# TK502_Frontpanel_LEDs.net
KiCad netlist of a schematic drawn in Altium Designer
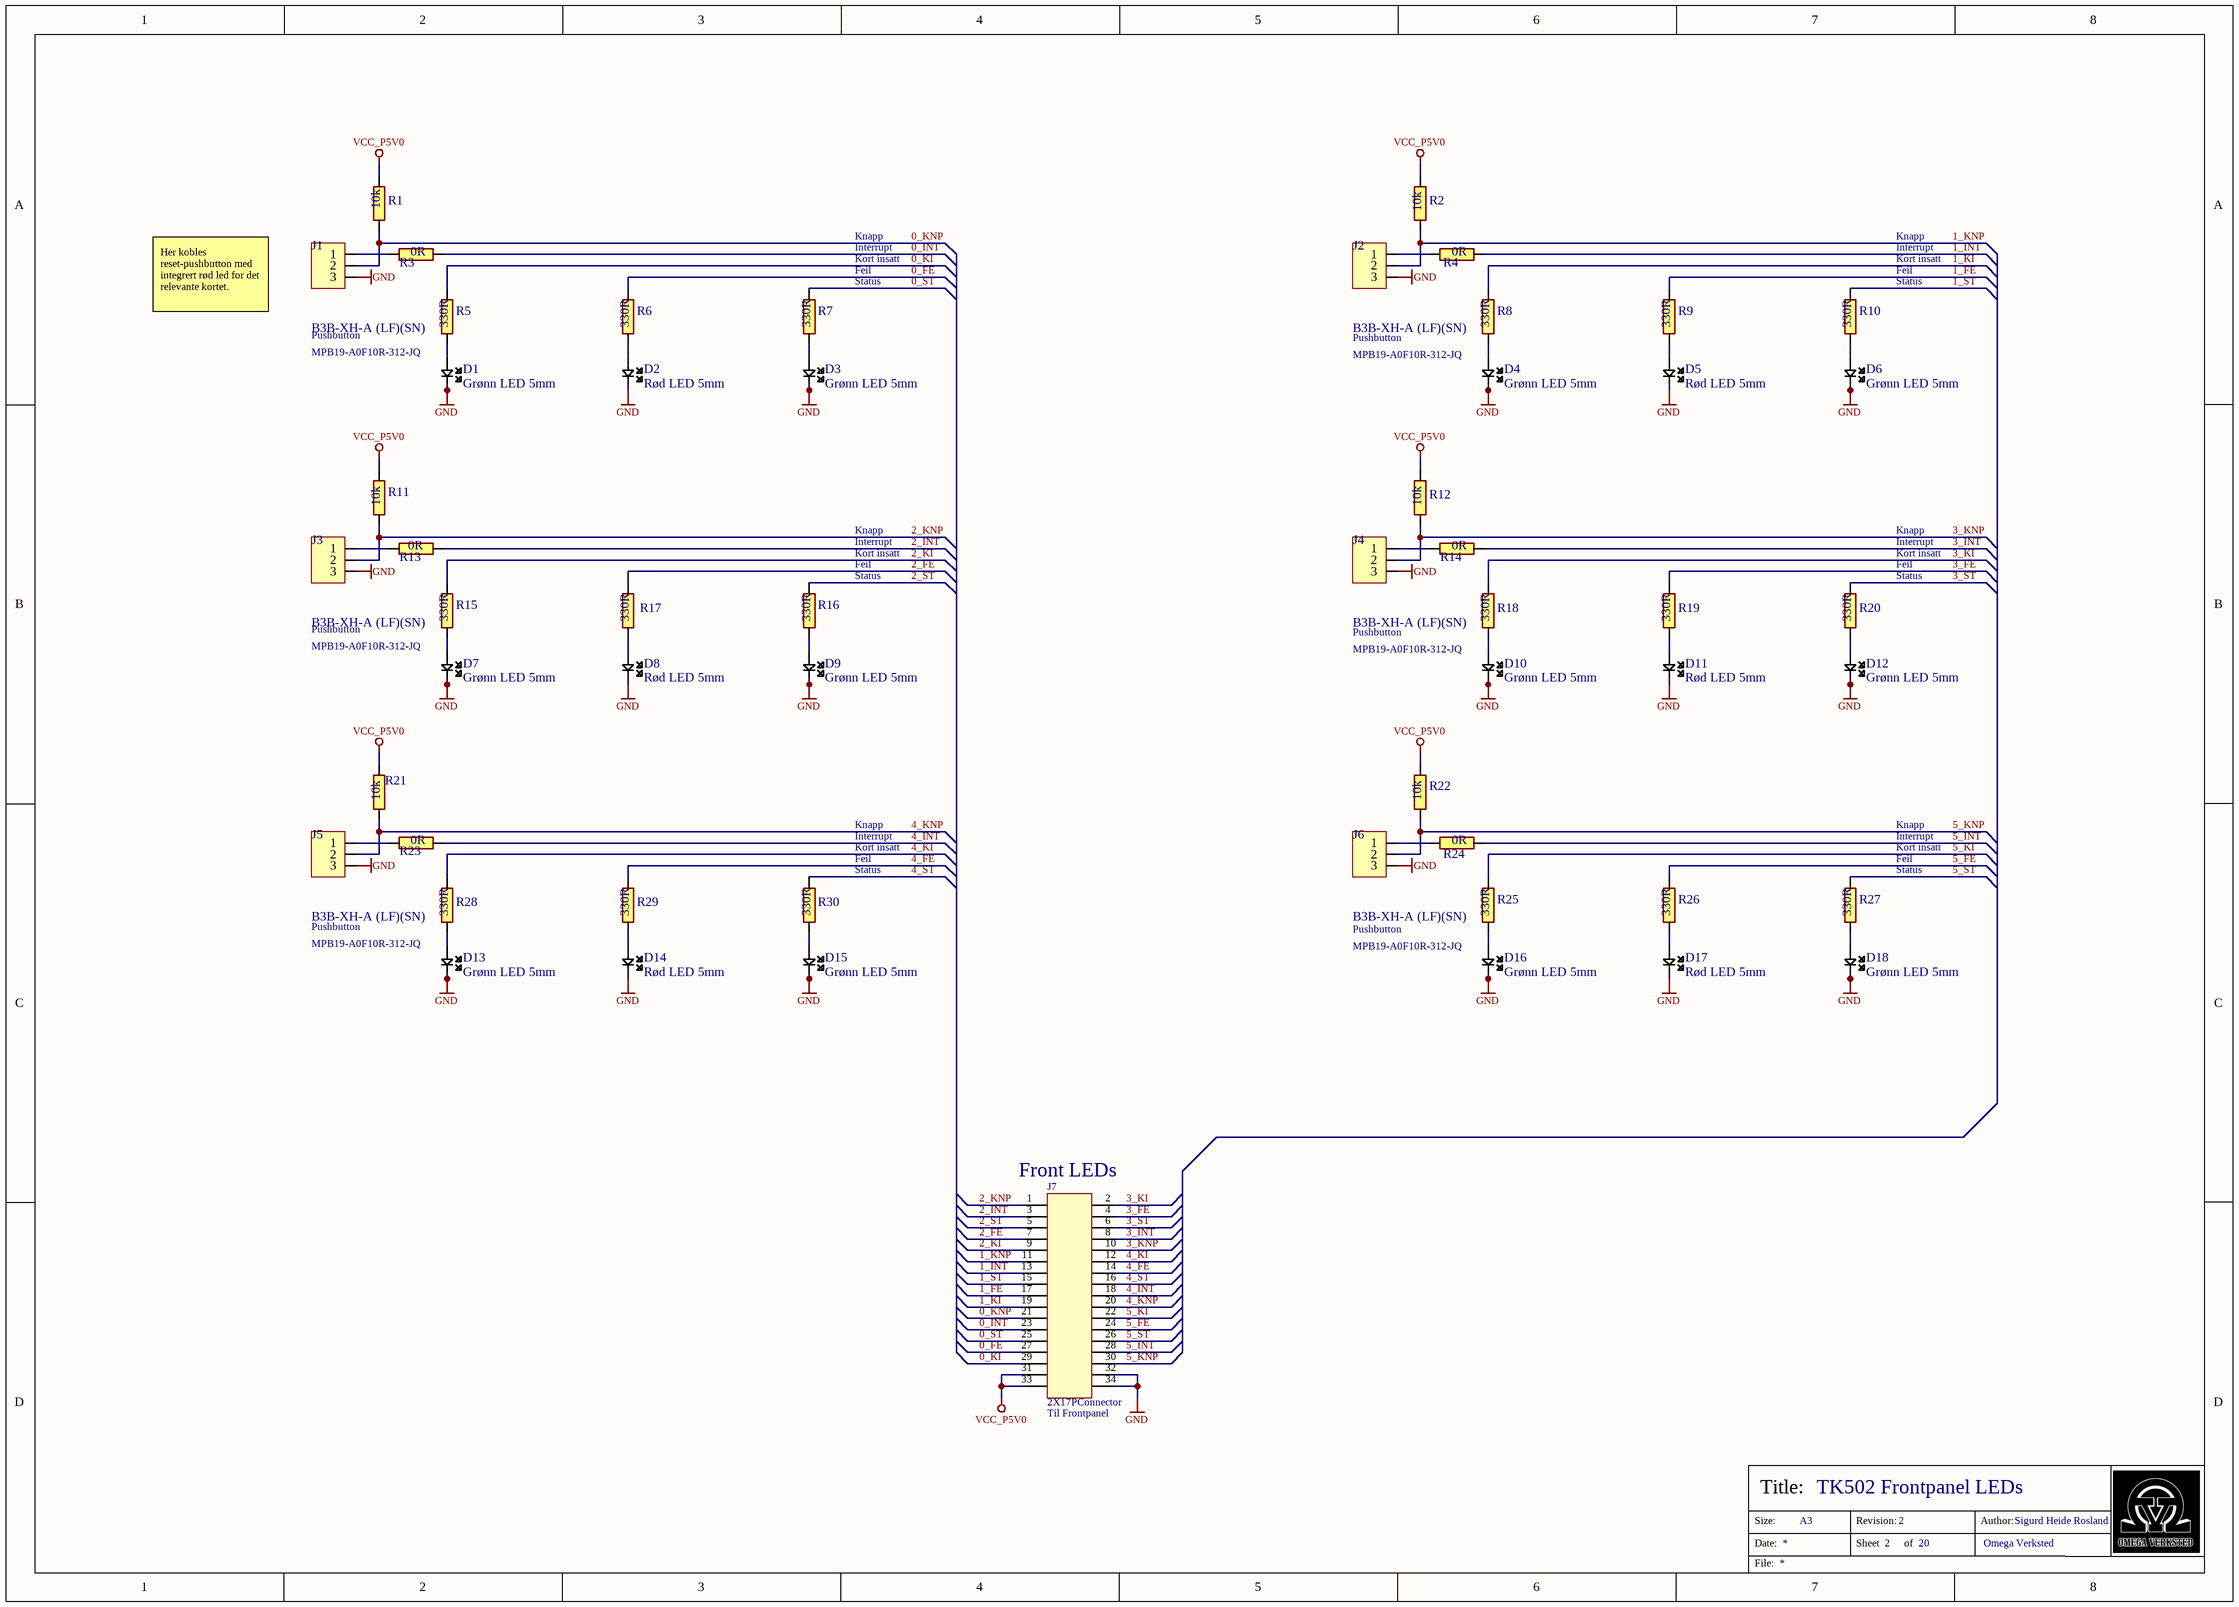
[diagram p0: TK502_Frontpanel_LEDs.SchDoc]

(export (version "E")
  (design (tool "Eeschema 10.0.6"))
  (components
    (comp (ref "D1")
      (value "Grønn LED 5mm")
      (footprint "LED254W7L870D500")
      (description "LED, Green, 5mm, 572 nm, 2.1 V, 20 mA, 150 mcd")
      (libsource (lib "OVLib_64") (part "LED"))
    )
    (comp (ref "D2")
      (value "Rød LED 5mm")
      (footprint "LED254W7L870D500")
      (description "LED, Red, 5mm, 643 nm, 1.8 V, 20 mA, 400 mcd")
      (libsource (lib "OVLib_64") (part "LED"))
    )
    (comp (ref "D3")
      (value "Grønn LED 5mm")
      (footprint "LED254W7L870D500")
      (description "LED, Green, 5mm, 572 nm, 2.1 V, 20 mA, 150 mcd")
      (libsource (lib "OVLib_64") (part "LED"))
    )
    (comp (ref "D4")
      (value "Grønn LED 5mm")
      (footprint "LED254W7L870D500")
      (description "LED, Green, 5mm, 572 nm, 2.1 V, 20 mA, 150 mcd")
      (libsource (lib "OVLib_64") (part "LED"))
    )
    (comp (ref "D5")
      (value "Rød LED 5mm")
      (footprint "LED254W7L870D500")
      (description "LED, Red, 5mm, 643 nm, 1.8 V, 20 mA, 400 mcd")
      (libsource (lib "OVLib_64") (part "LED"))
    )
    (comp (ref "D6")
      (value "Grønn LED 5mm")
      (footprint "LED254W7L870D500")
      (description "LED, Green, 5mm, 572 nm, 2.1 V, 20 mA, 150 mcd")
      (libsource (lib "OVLib_64") (part "LED"))
    )
    (comp (ref "D7")
      (value "Grønn LED 5mm")
      (footprint "LED254W7L870D500")
      (description "LED, Green, 5mm, 572 nm, 2.1 V, 20 mA, 150 mcd")
      (libsource (lib "OVLib_64") (part "LED"))
    )
    (comp (ref "D8")
      (value "Rød LED 5mm")
      (footprint "LED254W7L870D500")
      (description "LED, Red, 5mm, 643 nm, 1.8 V, 20 mA, 400 mcd")
      (libsource (lib "OVLib_64") (part "LED"))
    )
    (comp (ref "D9")
      (value "Grønn LED 5mm")
      (footprint "LED254W7L870D500")
      (description "LED, Green, 5mm, 572 nm, 2.1 V, 20 mA, 150 mcd")
      (libsource (lib "OVLib_64") (part "LED"))
    )
    (comp (ref "D10")
      (value "Grønn LED 5mm")
      (footprint "LED254W7L870D500")
      (description "LED, Green, 5mm, 572 nm, 2.1 V, 20 mA, 150 mcd")
      (libsource (lib "OVLib_64") (part "LED"))
    )
    (comp (ref "D11")
      (value "Rød LED 5mm")
      (footprint "LED254W7L870D500")
      (description "LED, Red, 5mm, 643 nm, 1.8 V, 20 mA, 400 mcd")
      (libsource (lib "OVLib_64") (part "LED"))
    )
    (comp (ref "D12")
      (value "Grønn LED 5mm")
      (footprint "LED254W7L870D500")
      (description "LED, Green, 5mm, 572 nm, 2.1 V, 20 mA, 150 mcd")
      (libsource (lib "OVLib_64") (part "LED"))
    )
    (comp (ref "D13")
      (value "Grønn LED 5mm")
      (footprint "LED254W7L870D500")
      (description "LED, Green, 5mm, 572 nm, 2.1 V, 20 mA, 150 mcd")
      (libsource (lib "OVLib_64") (part "LED"))
    )
    (comp (ref "D14")
      (value "Rød LED 5mm")
      (footprint "LED254W7L870D500")
      (description "LED, Red, 5mm, 643 nm, 1.8 V, 20 mA, 400 mcd")
      (libsource (lib "OVLib_64") (part "LED"))
    )
    (comp (ref "D15")
      (value "Grønn LED 5mm")
      (footprint "LED254W7L870D500")
      (description "LED, Green, 5mm, 572 nm, 2.1 V, 20 mA, 150 mcd")
      (libsource (lib "OVLib_64") (part "LED"))
    )
    (comp (ref "D16")
      (value "Grønn LED 5mm")
      (footprint "LED254W7L870D500")
      (description "LED, Green, 5mm, 572 nm, 2.1 V, 20 mA, 150 mcd")
      (libsource (lib "OVLib_64") (part "LED"))
    )
    (comp (ref "D17")
      (value "Rød LED 5mm")
      (footprint "LED254W7L870D500")
      (description "LED, Red, 5mm, 643 nm, 1.8 V, 20 mA, 400 mcd")
      (libsource (lib "OVLib_64") (part "LED"))
    )
    (comp (ref "D18")
      (value "Grønn LED 5mm")
      (footprint "LED254W7L870D500")
      (description "LED, Green, 5mm, 572 nm, 2.1 V, 20 mA, 150 mcd")
      (libsource (lib "OVLib_64") (part "LED"))
    )
    (comp (ref "J1")
      (value "B3B-XH-A (LF)(SN)")
      (footprint "JST_3P")
      (description "JST 3pin (pris pr. stk.)")
      (libsource (lib "OVLib_64") (part "3PConnector"))
    )
    (comp (ref "J2")
      (value "B3B-XH-A (LF)(SN)")
      (footprint "JST_3P")
      (description "JST 3pin (pris pr. stk.)")
      (libsource (lib "OVLib_64") (part "3PConnector"))
    )
    (comp (ref "J3")
      (value "B3B-XH-A (LF)(SN)")
      (footprint "JST_3P")
      (description "JST 3pin (pris pr. stk.)")
      (libsource (lib "OVLib_64") (part "3PConnector"))
    )
    (comp (ref "J4")
      (value "B3B-XH-A (LF)(SN)")
      (footprint "JST_3P")
      (description "JST 3pin (pris pr. stk.)")
      (libsource (lib "OVLib_64") (part "3PConnector"))
    )
    (comp (ref "J5")
      (value "B3B-XH-A (LF)(SN)")
      (footprint "JST_3P")
      (description "JST 3pin (pris pr. stk.)")
      (libsource (lib "OVLib_64") (part "3PConnector"))
    )
    (comp (ref "J6")
      (value "B3B-XH-A (LF)(SN)")
      (footprint "JST_3P")
      (description "JST 3pin (pris pr. stk.)")
      (libsource (lib "OVLib_64") (part "3PConnector"))
    )
    (comp (ref "J7")
      (value "2X17PConnector")
      (footprint "HDRV34W64P254_2X17_5070X900X900B")
      (description "Header")
      (libsource (lib "OVLib_64") (part "2X17PConnector"))
    )
    (comp (ref "R1")
      (value "10k")
      (footprint "RESC0603(1608)_N")
      (description "0.1W 1% Thick film resistor")
      (libsource (lib "OVLib_64") (part "Resistor2"))
    )
    (comp (ref "R2")
      (value "10k")
      (footprint "RESC0603(1608)_N")
      (description "0.1W 1% Thick film resistor")
      (libsource (lib "OVLib_64") (part "Resistor2"))
    )
    (comp (ref "R3")
      (value "0R")
      (footprint "RESC0603(1608)_N")
      (description "0.1W 1% Thick film resistor, Jumper")
      (libsource (lib "") (part "Resistor2_2"))
    )
    (comp (ref "R4")
      (value "0R")
      (footprint "RESC0603(1608)_N")
      (description "0.1W 1% Thick film resistor, Jumper")
      (libsource (lib "") (part "Resistor2_1"))
    )
    (comp (ref "R5")
      (value "330R")
      (footprint "RESC0603(1608)_N")
      (description "0.1W 1% Thick film resistor")
      (libsource (lib "OVLib_64") (part "Resistor2"))
    )
    (comp (ref "R6")
      (value "330R")
      (footprint "RESC0603(1608)_N")
      (description "0.1W 1% Thick film resistor")
      (libsource (lib "OVLib_64") (part "Resistor2"))
    )
    (comp (ref "R7")
      (value "330R")
      (footprint "RESC0603(1608)_N")
      (description "0.1W 1% Thick film resistor")
      (libsource (lib "OVLib_64") (part "Resistor2"))
    )
    (comp (ref "R8")
      (value "330R")
      (footprint "RESC0603(1608)_N")
      (description "0.1W 1% Thick film resistor")
      (libsource (lib "OVLib_64") (part "Resistor2"))
    )
    (comp (ref "R9")
      (value "330R")
      (footprint "RESC0603(1608)_N")
      (description "0.1W 1% Thick film resistor")
      (libsource (lib "OVLib_64") (part "Resistor2"))
    )
    (comp (ref "R10")
      (value "330R")
      (footprint "RESC0603(1608)_N")
      (description "0.1W 1% Thick film resistor")
      (libsource (lib "OVLib_64") (part "Resistor2"))
    )
    (comp (ref "R11")
      (value "10k")
      (footprint "RESC0603(1608)_N")
      (description "0.1W 1% Thick film resistor")
      (libsource (lib "OVLib_64") (part "Resistor2"))
    )
    (comp (ref "R12")
      (value "10k")
      (footprint "RESC0603(1608)_N")
      (description "0.1W 1% Thick film resistor")
      (libsource (lib "OVLib_64") (part "Resistor2"))
    )
    (comp (ref "R13")
      (value "0R")
      (footprint "RESC0603(1608)_N")
      (description "0.1W 1% Thick film resistor, Jumper")
      (libsource (lib "") (part "Resistor2_2"))
    )
    (comp (ref "R14")
      (value "0R")
      (footprint "RESC0603(1608)_N")
      (description "0.1W 1% Thick film resistor, Jumper")
      (libsource (lib "") (part "Resistor2_1"))
    )
    (comp (ref "R15")
      (value "330R")
      (footprint "RESC0603(1608)_N")
      (description "0.1W 1% Thick film resistor")
      (libsource (lib "OVLib_64") (part "Resistor2"))
    )
    (comp (ref "R16")
      (value "330R")
      (footprint "RESC0603(1608)_N")
      (description "0.1W 1% Thick film resistor")
      (libsource (lib "OVLib_64") (part "Resistor2"))
    )
    (comp (ref "R17")
      (value "330R")
      (footprint "RESC0603(1608)_N")
      (description "0.1W 1% Thick film resistor")
      (libsource (lib "OVLib_64") (part "Resistor2"))
    )
    (comp (ref "R18")
      (value "330R")
      (footprint "RESC0603(1608)_N")
      (description "0.1W 1% Thick film resistor")
      (libsource (lib "OVLib_64") (part "Resistor2"))
    )
    (comp (ref "R19")
      (value "330R")
      (footprint "RESC0603(1608)_N")
      (description "0.1W 1% Thick film resistor")
      (libsource (lib "OVLib_64") (part "Resistor2"))
    )
    (comp (ref "R20")
      (value "330R")
      (footprint "RESC0603(1608)_N")
      (description "0.1W 1% Thick film resistor")
      (libsource (lib "OVLib_64") (part "Resistor2"))
    )
    (comp (ref "R21")
      (value "10k")
      (footprint "RESC0603(1608)_N")
      (description "0.1W 1% Thick film resistor")
      (libsource (lib "OVLib_64") (part "Resistor2"))
    )
    (comp (ref "R22")
      (value "10k")
      (footprint "RESC0603(1608)_N")
      (description "0.1W 1% Thick film resistor")
      (libsource (lib "OVLib_64") (part "Resistor2"))
    )
    (comp (ref "R23")
      (value "0R")
      (footprint "RESC0603(1608)_N")
      (description "0.1W 1% Thick film resistor, Jumper")
      (libsource (lib "") (part "Resistor2_2"))
    )
    (comp (ref "R24")
      (value "0R")
      (footprint "RESC0603(1608)_N")
      (description "0.1W 1% Thick film resistor, Jumper")
      (libsource (lib "") (part "Resistor2_2"))
    )
    (comp (ref "R25")
      (value "330R")
      (footprint "RESC0603(1608)_N")
      (description "0.1W 1% Thick film resistor")
      (libsource (lib "OVLib_64") (part "Resistor2"))
    )
    (comp (ref "R26")
      (value "330R")
      (footprint "RESC0603(1608)_N")
      (description "0.1W 1% Thick film resistor")
      (libsource (lib "OVLib_64") (part "Resistor2"))
    )
    (comp (ref "R27")
      (value "330R")
      (footprint "RESC0603(1608)_N")
      (description "0.1W 1% Thick film resistor")
      (libsource (lib "OVLib_64") (part "Resistor2"))
    )
    (comp (ref "R28")
      (value "330R")
      (footprint "RESC0603(1608)_N")
      (description "0.1W 1% Thick film resistor")
      (libsource (lib "OVLib_64") (part "Resistor2"))
    )
    (comp (ref "R29")
      (value "330R")
      (footprint "RESC0603(1608)_N")
      (description "0.1W 1% Thick film resistor")
      (libsource (lib "OVLib_64") (part "Resistor2"))
    )
    (comp (ref "R30")
      (value "330R")
      (footprint "RESC0603(1608)_N")
      (description "0.1W 1% Thick film resistor")
      (libsource (lib "OVLib_64") (part "Resistor2"))
    )
  )
  (nets
    (net (code "1") (name "/0_FE") (class "Default")
      (node (ref "J7") (pin "27") (pinfunction "27_27") (pintype "passive"))
      (node (ref "R6") (pin "2") (pinfunction "2_2") (pintype "passive"))
    )
    (net (code "2") (name "/0_INT") (class "Default")
      (node (ref "J7") (pin "23") (pinfunction "23_23") (pintype "passive"))
      (node (ref "R3") (pin "1") (pinfunction "1_1") (pintype "passive"))
    )
    (net (code "3") (name "/0_KI") (class "Default")
      (node (ref "J7") (pin "29") (pinfunction "29_29") (pintype "passive"))
      (node (ref "R5") (pin "2") (pinfunction "2_2") (pintype "passive"))
    )
    (net (code "4") (name "/0_KNP") (class "Default")
      (node (ref "J1") (pin "2") (pinfunction "2_2") (pintype "passive"))
      (node (ref "J7") (pin "21") (pinfunction "21_21") (pintype "passive"))
      (node (ref "R1") (pin "1") (pinfunction "1_1") (pintype "passive"))
    )
    (net (code "5") (name "/0_ST") (class "Default")
      (node (ref "J7") (pin "25") (pinfunction "25_25") (pintype "passive"))
      (node (ref "R7") (pin "2") (pinfunction "2_2") (pintype "passive"))
    )
    (net (code "6") (name "/1_FE") (class "Default")
      (node (ref "J7") (pin "17") (pinfunction "17_17") (pintype "passive"))
      (node (ref "R9") (pin "2") (pinfunction "2_2") (pintype "passive"))
    )
    (net (code "7") (name "/1_INT") (class "Default")
      (node (ref "J7") (pin "13") (pinfunction "13_13") (pintype "passive"))
      (node (ref "R4") (pin "1") (pinfunction "1_1") (pintype "passive"))
    )
    (net (code "8") (name "/1_KI") (class "Default")
      (node (ref "J7") (pin "19") (pinfunction "19_19") (pintype "passive"))
      (node (ref "R8") (pin "2") (pinfunction "2_2") (pintype "passive"))
    )
    (net (code "9") (name "/1_KNP") (class "Default")
      (node (ref "J2") (pin "2") (pinfunction "2_2") (pintype "passive"))
      (node (ref "J7") (pin "11") (pinfunction "11_11") (pintype "passive"))
      (node (ref "R2") (pin "1") (pinfunction "1_1") (pintype "passive"))
    )
    (net (code "10") (name "/1_ST") (class "Default")
      (node (ref "J7") (pin "15") (pinfunction "15_15") (pintype "passive"))
      (node (ref "R10") (pin "2") (pinfunction "2_2") (pintype "passive"))
    )
    (net (code "11") (name "/2_FE") (class "Default")
      (node (ref "J7") (pin "7") (pinfunction "7_7") (pintype "passive"))
      (node (ref "R17") (pin "2") (pinfunction "2_2") (pintype "passive"))
    )
    (net (code "12") (name "/2_INT") (class "Default")
      (node (ref "J7") (pin "3") (pinfunction "3_3") (pintype "passive"))
      (node (ref "R13") (pin "1") (pinfunction "1_1") (pintype "passive"))
    )
    (net (code "13") (name "/2_KI") (class "Default")
      (node (ref "J7") (pin "9") (pinfunction "9_9") (pintype "passive"))
      (node (ref "R15") (pin "2") (pinfunction "2_2") (pintype "passive"))
    )
    (net (code "14") (name "/2_KNP") (class "Default")
      (node (ref "J3") (pin "2") (pinfunction "2_2") (pintype "passive"))
      (node (ref "J7") (pin "1") (pinfunction "1_1") (pintype "passive"))
      (node (ref "R11") (pin "1") (pinfunction "1_1") (pintype "passive"))
    )
    (net (code "15") (name "/2_ST") (class "Default")
      (node (ref "J7") (pin "5") (pinfunction "5_5") (pintype "passive"))
      (node (ref "R16") (pin "2") (pinfunction "2_2") (pintype "passive"))
    )
    (net (code "16") (name "/3_FE") (class "Default")
      (node (ref "J7") (pin "4") (pinfunction "4_4") (pintype "passive"))
      (node (ref "R19") (pin "2") (pinfunction "2_2") (pintype "passive"))
    )
    (net (code "17") (name "/3_INT") (class "Default")
      (node (ref "J7") (pin "8") (pinfunction "8_8") (pintype "passive"))
      (node (ref "R14") (pin "1") (pinfunction "1_1") (pintype "passive"))
    )
    (net (code "18") (name "/3_KI") (class "Default")
      (node (ref "J7") (pin "2") (pinfunction "2_2") (pintype "passive"))
      (node (ref "R18") (pin "2") (pinfunction "2_2") (pintype "passive"))
    )
    (net (code "19") (name "/3_KNP") (class "Default")
      (node (ref "J4") (pin "2") (pinfunction "2_2") (pintype "passive"))
      (node (ref "J7") (pin "10") (pinfunction "10_10") (pintype "passive"))
      (node (ref "R12") (pin "1") (pinfunction "1_1") (pintype "passive"))
    )
    (net (code "20") (name "/3_ST") (class "Default")
      (node (ref "J7") (pin "6") (pinfunction "6_6") (pintype "passive"))
      (node (ref "R20") (pin "2") (pinfunction "2_2") (pintype "passive"))
    )
    (net (code "21") (name "/4_FE") (class "Default")
      (node (ref "J7") (pin "14") (pinfunction "14_14") (pintype "passive"))
      (node (ref "R29") (pin "2") (pinfunction "2_2") (pintype "passive"))
    )
    (net (code "22") (name "/4_INT") (class "Default")
      (node (ref "J7") (pin "18") (pinfunction "18_18") (pintype "passive"))
      (node (ref "R23") (pin "1") (pinfunction "1_1") (pintype "passive"))
    )
    (net (code "23") (name "/4_KI") (class "Default")
      (node (ref "J7") (pin "12") (pinfunction "12_12") (pintype "passive"))
      (node (ref "R28") (pin "2") (pinfunction "2_2") (pintype "passive"))
    )
    (net (code "24") (name "/4_KNP") (class "Default")
      (node (ref "J5") (pin "2") (pinfunction "2_2") (pintype "passive"))
      (node (ref "J7") (pin "20") (pinfunction "20_20") (pintype "passive"))
      (node (ref "R21") (pin "1") (pinfunction "1_1") (pintype "passive"))
    )
    (net (code "25") (name "/4_ST") (class "Default")
      (node (ref "J7") (pin "16") (pinfunction "16_16") (pintype "passive"))
      (node (ref "R30") (pin "2") (pinfunction "2_2") (pintype "passive"))
    )
    (net (code "26") (name "/5_FE") (class "Default")
      (node (ref "J7") (pin "24") (pinfunction "24_24") (pintype "passive"))
      (node (ref "R26") (pin "2") (pinfunction "2_2") (pintype "passive"))
    )
    (net (code "27") (name "/5_INT") (class "Default")
      (node (ref "J7") (pin "28") (pinfunction "28_28") (pintype "passive"))
      (node (ref "R24") (pin "1") (pinfunction "1_1") (pintype "passive"))
    )
    (net (code "28") (name "/5_KI") (class "Default")
      (node (ref "J7") (pin "22") (pinfunction "22_22") (pintype "passive"))
      (node (ref "R25") (pin "2") (pinfunction "2_2") (pintype "passive"))
    )
    (net (code "29") (name "/5_KNP") (class "Default")
      (node (ref "J6") (pin "2") (pinfunction "2_2") (pintype "passive"))
      (node (ref "J7") (pin "30") (pinfunction "30_30") (pintype "passive"))
      (node (ref "R22") (pin "1") (pinfunction "1_1") (pintype "passive"))
    )
    (net (code "30") (name "/5_ST") (class "Default")
      (node (ref "J7") (pin "26") (pinfunction "26_26") (pintype "passive"))
      (node (ref "R27") (pin "2") (pinfunction "2_2") (pintype "passive"))
    )
    (net (code "31") (name "GND") (class "Default")
      (node (ref "D1") (pin "2") (pinfunction "2_2") (pintype "passive"))
      (node (ref "D10") (pin "2") (pinfunction "2_2") (pintype "passive"))
      (node (ref "D11") (pin "2") (pinfunction "2_2") (pintype "passive"))
      (node (ref "D12") (pin "2") (pinfunction "2_2") (pintype "passive"))
      (node (ref "D13") (pin "2") (pinfunction "2_2") (pintype "passive"))
      (node (ref "D14") (pin "2") (pinfunction "2_2") (pintype "passive"))
      (node (ref "D15") (pin "2") (pinfunction "2_2") (pintype "passive"))
      (node (ref "D16") (pin "2") (pinfunction "2_2") (pintype "passive"))
      (node (ref "D17") (pin "2") (pinfunction "2_2") (pintype "passive"))
      (node (ref "D18") (pin "2") (pinfunction "2_2") (pintype "passive"))
      (node (ref "D2") (pin "2") (pinfunction "2_2") (pintype "passive"))
      (node (ref "D3") (pin "2") (pinfunction "2_2") (pintype "passive"))
      (node (ref "D4") (pin "2") (pinfunction "2_2") (pintype "passive"))
      (node (ref "D5") (pin "2") (pinfunction "2_2") (pintype "passive"))
      (node (ref "D6") (pin "2") (pinfunction "2_2") (pintype "passive"))
      (node (ref "D7") (pin "2") (pinfunction "2_2") (pintype "passive"))
      (node (ref "D8") (pin "2") (pinfunction "2_2") (pintype "passive"))
      (node (ref "D9") (pin "2") (pinfunction "2_2") (pintype "passive"))
      (node (ref "J1") (pin "3") (pinfunction "3_3") (pintype "passive"))
      (node (ref "J2") (pin "3") (pinfunction "3_3") (pintype "passive"))
      (node (ref "J3") (pin "3") (pinfunction "3_3") (pintype "passive"))
      (node (ref "J4") (pin "3") (pinfunction "3_3") (pintype "passive"))
      (node (ref "J5") (pin "3") (pinfunction "3_3") (pintype "passive"))
      (node (ref "J6") (pin "3") (pinfunction "3_3") (pintype "passive"))
      (node (ref "J7") (pin "32") (pinfunction "32_32") (pintype "passive"))
      (node (ref "J7") (pin "34") (pinfunction "34_34") (pintype "passive"))
    )
    (net (code "32") (name "Net-(D1-Pad1)") (class "Default")
      (node (ref "D1") (pin "1") (pinfunction "1_1") (pintype "passive"))
      (node (ref "R5") (pin "1") (pinfunction "1_1") (pintype "passive"))
    )
    (net (code "33") (name "Net-(D2-Pad1)") (class "Default")
      (node (ref "D2") (pin "1") (pinfunction "1_1") (pintype "passive"))
      (node (ref "R6") (pin "1") (pinfunction "1_1") (pintype "passive"))
    )
    (net (code "34") (name "Net-(D3-Pad1)") (class "Default")
      (node (ref "D3") (pin "1") (pinfunction "1_1") (pintype "passive"))
      (node (ref "R7") (pin "1") (pinfunction "1_1") (pintype "passive"))
    )
    (net (code "35") (name "Net-(D4-Pad1)") (class "Default")
      (node (ref "D4") (pin "1") (pinfunction "1_1") (pintype "passive"))
      (node (ref "R8") (pin "1") (pinfunction "1_1") (pintype "passive"))
    )
    (net (code "36") (name "Net-(D5-Pad1)") (class "Default")
      (node (ref "D5") (pin "1") (pinfunction "1_1") (pintype "passive"))
      (node (ref "R9") (pin "1") (pinfunction "1_1") (pintype "passive"))
    )
    (net (code "37") (name "Net-(D6-Pad1)") (class "Default")
      (node (ref "D6") (pin "1") (pinfunction "1_1") (pintype "passive"))
      (node (ref "R10") (pin "1") (pinfunction "1_1") (pintype "passive"))
    )
    (net (code "38") (name "Net-(D7-Pad1)") (class "Default")
      (node (ref "D7") (pin "1") (pinfunction "1_1") (pintype "passive"))
      (node (ref "R15") (pin "1") (pinfunction "1_1") (pintype "passive"))
    )
    (net (code "39") (name "Net-(D8-Pad1)") (class "Default")
      (node (ref "D8") (pin "1") (pinfunction "1_1") (pintype "passive"))
      (node (ref "R17") (pin "1") (pinfunction "1_1") (pintype "passive"))
    )
    (net (code "40") (name "Net-(D9-Pad1)") (class "Default")
      (node (ref "D9") (pin "1") (pinfunction "1_1") (pintype "passive"))
      (node (ref "R16") (pin "1") (pinfunction "1_1") (pintype "passive"))
    )
    (net (code "41") (name "Net-(D10-Pad1)") (class "Default")
      (node (ref "D10") (pin "1") (pinfunction "1_1") (pintype "passive"))
      (node (ref "R18") (pin "1") (pinfunction "1_1") (pintype "passive"))
    )
    (net (code "42") (name "Net-(D11-Pad1)") (class "Default")
      (node (ref "D11") (pin "1") (pinfunction "1_1") (pintype "passive"))
      (node (ref "R19") (pin "1") (pinfunction "1_1") (pintype "passive"))
    )
    (net (code "43") (name "Net-(D12-Pad1)") (class "Default")
      (node (ref "D12") (pin "1") (pinfunction "1_1") (pintype "passive"))
      (node (ref "R20") (pin "1") (pinfunction "1_1") (pintype "passive"))
    )
    (net (code "44") (name "Net-(D13-Pad1)") (class "Default")
      (node (ref "D13") (pin "1") (pinfunction "1_1") (pintype "passive"))
      (node (ref "R28") (pin "1") (pinfunction "1_1") (pintype "passive"))
    )
    (net (code "45") (name "Net-(D14-Pad1)") (class "Default")
      (node (ref "D14") (pin "1") (pinfunction "1_1") (pintype "passive"))
      (node (ref "R29") (pin "1") (pinfunction "1_1") (pintype "passive"))
    )
    (net (code "46") (name "Net-(D15-Pad1)") (class "Default")
      (node (ref "D15") (pin "1") (pinfunction "1_1") (pintype "passive"))
      (node (ref "R30") (pin "1") (pinfunction "1_1") (pintype "passive"))
    )
    (net (code "47") (name "Net-(D16-Pad1)") (class "Default")
      (node (ref "D16") (pin "1") (pinfunction "1_1") (pintype "passive"))
      (node (ref "R25") (pin "1") (pinfunction "1_1") (pintype "passive"))
    )
    (net (code "48") (name "Net-(D17-Pad1)") (class "Default")
      (node (ref "D17") (pin "1") (pinfunction "1_1") (pintype "passive"))
      (node (ref "R26") (pin "1") (pinfunction "1_1") (pintype "passive"))
    )
    (net (code "49") (name "Net-(D18-Pad1)") (class "Default")
      (node (ref "D18") (pin "1") (pinfunction "1_1") (pintype "passive"))
      (node (ref "R27") (pin "1") (pinfunction "1_1") (pintype "passive"))
    )
    (net (code "50") (name "Net-(J1-Pad1)") (class "Default")
      (node (ref "J1") (pin "1") (pinfunction "1_1") (pintype "passive"))
      (node (ref "R3") (pin "2") (pinfunction "2_2") (pintype "passive"))
    )
    (net (code "51") (name "Net-(J2-Pad1)") (class "Default")
      (node (ref "J2") (pin "1") (pinfunction "1_1") (pintype "passive"))
      (node (ref "R4") (pin "2") (pinfunction "2_2") (pintype "passive"))
    )
    (net (code "52") (name "Net-(J3-Pad1)") (class "Default")
      (node (ref "J3") (pin "1") (pinfunction "1_1") (pintype "passive"))
      (node (ref "R13") (pin "2") (pinfunction "2_2") (pintype "passive"))
    )
    (net (code "53") (name "Net-(J4-Pad1)") (class "Default")
      (node (ref "J4") (pin "1") (pinfunction "1_1") (pintype "passive"))
      (node (ref "R14") (pin "2") (pinfunction "2_2") (pintype "passive"))
    )
    (net (code "54") (name "Net-(J5-Pad1)") (class "Default")
      (node (ref "J5") (pin "1") (pinfunction "1_1") (pintype "passive"))
      (node (ref "R23") (pin "2") (pinfunction "2_2") (pintype "passive"))
    )
    (net (code "55") (name "Net-(J6-Pad1)") (class "Default")
      (node (ref "J6") (pin "1") (pinfunction "1_1") (pintype "passive"))
      (node (ref "R24") (pin "2") (pinfunction "2_2") (pintype "passive"))
    )
    (net (code "56") (name "VCC_P5V0") (class "Default")
      (node (ref "J7") (pin "31") (pinfunction "31_31") (pintype "passive"))
      (node (ref "J7") (pin "33") (pinfunction "33_33") (pintype "passive"))
      (node (ref "R1") (pin "2") (pinfunction "2_2") (pintype "passive"))
      (node (ref "R11") (pin "2") (pinfunction "2_2") (pintype "passive"))
      (node (ref "R12") (pin "2") (pinfunction "2_2") (pintype "passive"))
      (node (ref "R2") (pin "2") (pinfunction "2_2") (pintype "passive"))
      (node (ref "R21") (pin "2") (pinfunction "2_2") (pintype "passive"))
      (node (ref "R22") (pin "2") (pinfunction "2_2") (pintype "passive"))
    )
  )
)
